# General.net
KiCad netlist of a schematic drawn in Altium Designer
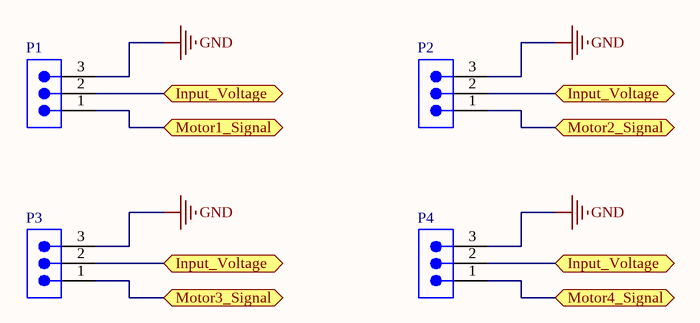
[diagram p0: General.SchDoc]

(export (version "E")
  (design (tool "Eeschema 10.0.6"))
  (components
    (comp (ref "P1")
      (value "M1")
      (footprint "61900311121")
      (libsource (lib "Altium Content Vault") (part "Header_Male_1R_03P"))
    )
    (comp (ref "P2")
      (value "M2")
      (footprint "61900311121")
      (libsource (lib "Altium Content Vault") (part "Header_Male_1R_03P"))
    )
    (comp (ref "P3")
      (value "M3")
      (footprint "61900311121")
      (libsource (lib "Altium Content Vault") (part "Header_Male_1R_03P"))
    )
    (comp (ref "P4")
      (value "M4")
      (footprint "61900311121")
      (libsource (lib "Altium Content Vault") (part "Header_Male_1R_03P"))
    )
  )
  (nets
    (net (code "1") (name "/Input_Voltage") (class "Default")
      (node (ref "P1") (pin "2") (pinfunction "2_2") (pintype "passive"))
      (node (ref "P2") (pin "2") (pinfunction "2_2") (pintype "passive"))
      (node (ref "P3") (pin "2") (pinfunction "2_2") (pintype "passive"))
      (node (ref "P4") (pin "2") (pinfunction "2_2") (pintype "passive"))
    )
    (net (code "2") (name "/Motor1_Signal") (class "Default")
      (node (ref "P1") (pin "1") (pinfunction "1_1") (pintype "passive"))
    )
    (net (code "3") (name "/Motor2_Signal") (class "Default")
      (node (ref "P2") (pin "1") (pinfunction "1_1") (pintype "passive"))
    )
    (net (code "4") (name "/Motor3_Signal") (class "Default")
      (node (ref "P3") (pin "1") (pinfunction "1_1") (pintype "passive"))
    )
    (net (code "5") (name "/Motor4_Signal") (class "Default")
      (node (ref "P4") (pin "1") (pinfunction "1_1") (pintype "passive"))
    )
    (net (code "6") (name "GND") (class "Default")
      (node (ref "P1") (pin "3") (pinfunction "3_3") (pintype "passive"))
      (node (ref "P2") (pin "3") (pinfunction "3_3") (pintype "passive"))
      (node (ref "P3") (pin "3") (pinfunction "3_3") (pintype "passive"))
      (node (ref "P4") (pin "3") (pinfunction "3_3") (pintype "passive"))
    )
  )
)
